# implant_5_3_marino5_doubleboost_3_8mm.net
KiCad netlist of a schematic drawn in EAGLE
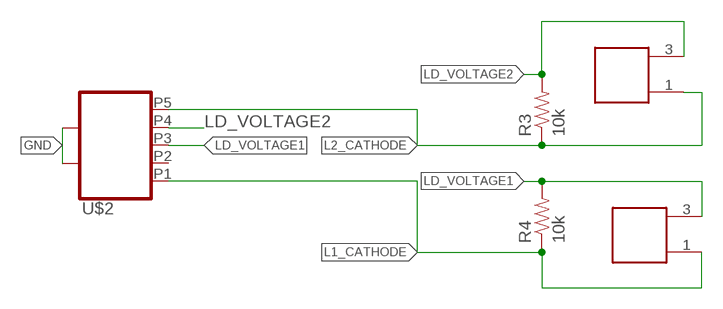
[diagram p0: schematic, sheet 1]

(export (version "E")
  (design (tool "Eeschema 10.0.6"))
  (components
    (comp (ref "R3")
      (value "10k")
      (footprint "eagle-import:0805")
      (libsource (lib "eagle-import") (part "RESISTOR0805-RES"))
    )
    (comp (ref "R4")
      (value "10k")
      (footprint "eagle-import:0805")
      (libsource (lib "eagle-import") (part "RESISTOR0805-RES"))
    )
    (comp (ref "U$2")
      (value "USB_MICRO_SOCKET_VERT")
      (footprint "eagle-import:USB_VERT_MICRO_SMD")
      (libsource (lib "eagle-import") (part "USB_MICRO_SOCKET_VERT"))
    )
    (comp (ref "U$4")
      (value "TEST1")
      (footprint "eagle-import:LASERDIODE_3.8_NEW")
      (libsource (lib "eagle-import") (part "TEST1"))
    )
    (comp (ref "U$5")
      (value "TEST1")
      (footprint "eagle-import:LASERDIODE_3.8_NEW")
      (libsource (lib "eagle-import") (part "TEST1"))
    )
  )
  (nets
    (net (code "1") (name "GND") (class "Default")
      (node (ref "U$2") (pin "P$1") (pinfunction "P$1_P$1") (pintype "bidirectional"))
      (node (ref "U$2") (pin "P$2") (pinfunction "P$2_P$2") (pintype "bidirectional"))
      (node (ref "U$2") (pin "P$3") (pinfunction "P$2_P$3") (pintype "bidirectional"))
    )
    (net (code "2") (name "L1_CATHODE") (class "Default")
      (node (ref "R4") (pin "1") (pinfunction "1_1") (pintype "passive"))
      (node (ref "U$2") (pin "P1") (pinfunction "P1_P1") (pintype "bidirectional"))
      (node (ref "U$5") (pin "1") (pinfunction "1_1") (pintype "bidirectional"))
    )
    (net (code "3") (name "L2_CATHODE") (class "Default")
      (node (ref "R3") (pin "1") (pinfunction "1_1") (pintype "passive"))
      (node (ref "U$2") (pin "P5") (pinfunction "P5_P5") (pintype "bidirectional"))
      (node (ref "U$4") (pin "1") (pinfunction "1_1") (pintype "bidirectional"))
    )
    (net (code "4") (name "LD_VOLTAGE1") (class "Default")
      (node (ref "R4") (pin "2") (pinfunction "2_2") (pintype "passive"))
      (node (ref "U$2") (pin "P3") (pinfunction "P3_P3") (pintype "bidirectional"))
      (node (ref "U$5") (pin "3") (pinfunction "3_3") (pintype "bidirectional"))
    )
    (net (code "5") (name "LD_VOLTAGE2") (class "Default")
      (node (ref "R3") (pin "2") (pinfunction "2_2") (pintype "passive"))
      (node (ref "U$2") (pin "P4") (pinfunction "P4_P4") (pintype "bidirectional"))
      (node (ref "U$4") (pin "3") (pinfunction "3_3") (pintype "bidirectional"))
    )
    (net (code "6") (name "unconnected-(U$2-PadP2)") (class "Default")
      (node (ref "U$2") (pin "P2") (pinfunction "P2_P2") (pintype "bidirectional"))
    )
  )
)
